# Touch_Sensing.net
KiCad netlist of a schematic drawn in Altium Designer
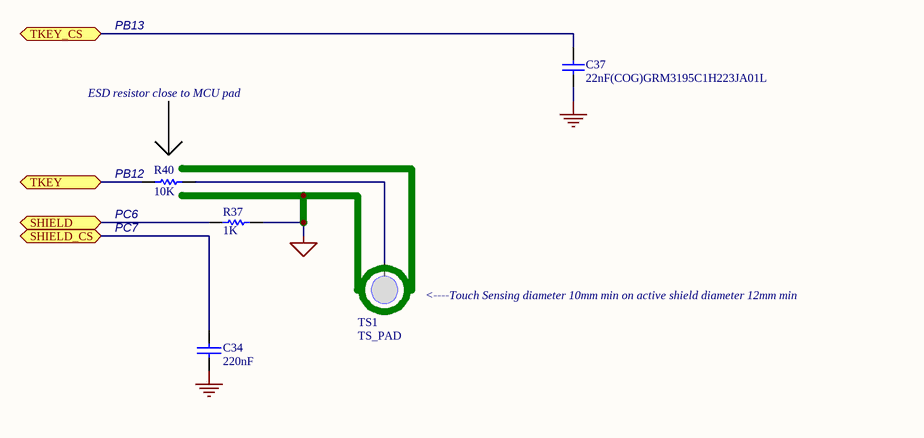
[diagram p0: Touch Sensing.SchDoc]

(export (version "E")
  (design (tool "Eeschema 10.0.6"))
  (components
    (comp (ref "C34")
      (value "220nF")
      (footprint "0603C")
      (description "Capacitor")
      (libsource (lib "*") (part "CAP"))
    )
    (comp (ref "C37")
      (value "22nF(COG)GRM3195C1H223JA01L")
      (footprint "1206C")
      (description "Capacitor")
      (fields (field (name "PUBLISHER") "Altium Limited"))
      (libsource (lib "Miscellaneous Devices") (part "CAP"))
    )
    (comp (ref "R37")
      (value "1K")
      (footprint "0402R")
      (description "Resistor")
      (fields (field (name "PUBLISHER") "Altium Limited"))
      (libsource (lib "Miscellaneous Devices") (part "Res1"))
    )
    (comp (ref "R40")
      (value "10K")
      (footprint "0402R")
      (description "Resistor")
      (fields (field (name "PUBLISHER") "Altium Limited"))
      (libsource (lib "Miscellaneous Devices") (part "Res1"))
    )
    (comp (ref "TS1") (value "TS_PAD") (footprint "TS_PAD") (libsource (lib "MB819") (part "TS_PAD")))
  )
  (nets
    (net (code "1") (name "/SHIELD") (class "Default")
      (node (ref "R37") (pin "1") (pinfunction "1_1") (pintype "passive"))
    )
    (net (code "2") (name "/SHIELD_CS") (class "Default")
      (node (ref "C34") (pin "2") (pinfunction "2_2") (pintype "passive"))
    )
    (net (code "3") (name "/TKEY") (class "Default")
      (node (ref "R40") (pin "1") (pinfunction "1_1") (pintype "passive"))
    )
    (net (code "4") (name "/TKEY_CS") (class "Default")
      (node (ref "C37") (pin "2") (pinfunction "2_2") (pintype "passive"))
    )
    (net (code "5") (name "GND") (class "Default")
      (node (ref "C34") (pin "1") (pinfunction "1_1") (pintype "passive"))
      (node (ref "C37") (pin "1") (pinfunction "1_1") (pintype "passive"))
    )
    (net (code "6") (name "Net-(R40-Pad2)") (class "Default")
      (node (ref "R40") (pin "2") (pinfunction "2_2") (pintype "passive"))
      (node (ref "TS1") (pin "1") (pinfunction "1_1") (pintype "passive"))
    )
    (net (code "7") (name "TS_SHIELD") (class "Default")
      (node (ref "R37") (pin "2") (pinfunction "2_2") (pintype "passive"))
    )
  )
)
